# SpringReverbRev2_1_combined.net
KiCad netlist of a schematic drawn in EAGLE
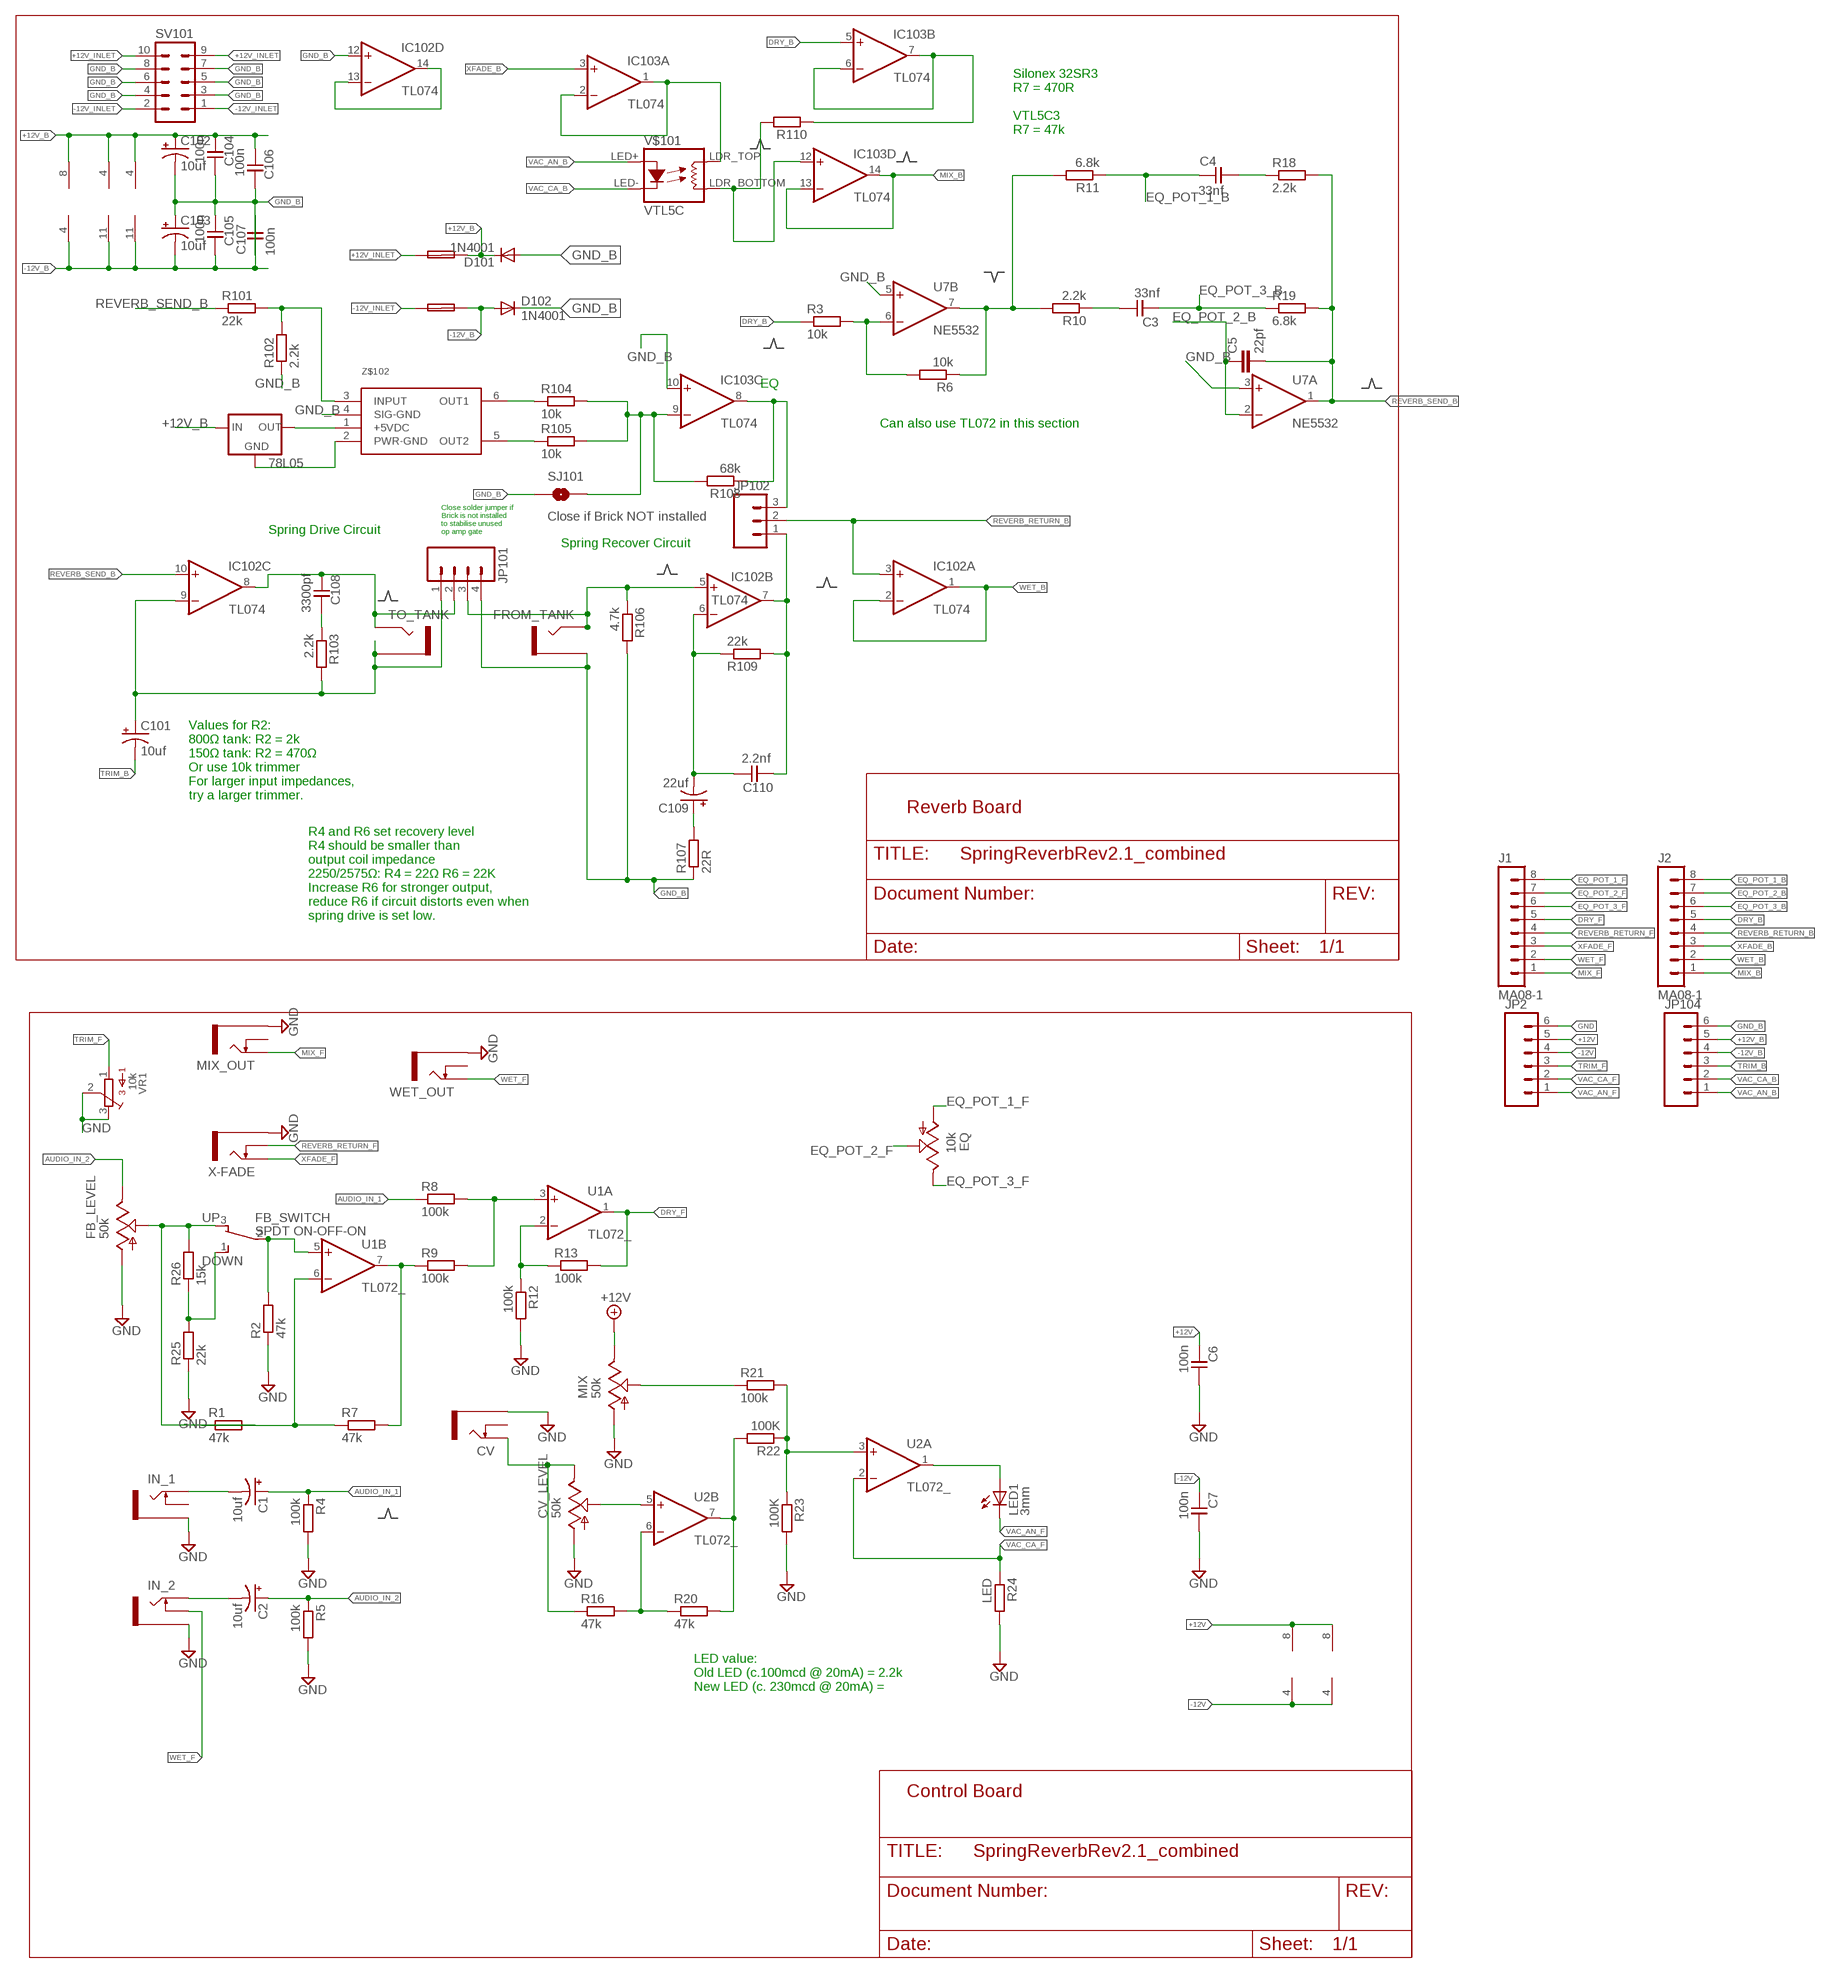
[diagram p0: schematic, sheet 1]

(export (version "E")
  (design (tool "Eeschema 10.0.6"))
  (components
    (comp (ref "78L05")
      (value "78LXX")
      (footprint "eagle-import:78LXX")
      (libsource (lib "eagle-import") (part "78LXX"))
    )
    (comp (ref "C1")
      (value "10uf")
      (footprint "eagle-import:050_020")
      (libsource (lib "eagle-import") (part "050"))
    )
    (comp (ref "C2")
      (value "10uf")
      (footprint "eagle-import:050_020")
      (libsource (lib "eagle-import") (part "050"))
    )
    (comp (ref "C3")
      (value "33nf")
      (footprint "eagle-import:C050-024X044")
      (libsource (lib "eagle-import") (part "C-EU050-024X044"))
    )
    (comp (ref "C4")
      (value "33nf")
      (footprint "eagle-import:C050-024X044")
      (libsource (lib "eagle-import") (part "C-EU050-024X044"))
    )
    (comp (ref "C5")
      (value "22pf")
      (footprint "eagle-import:050X030_025")
      (libsource (lib "eagle-import") (part "050X030_0251"))
    )
    (comp (ref "C6")
      (value "100n")
      (footprint "eagle-import:C050-024X044")
      (libsource (lib "eagle-import") (part "C-EU050-024X044"))
    )
    (comp (ref "C7")
      (value "100n")
      (footprint "eagle-import:C050-024X044")
      (libsource (lib "eagle-import") (part "C-EU050-024X044"))
    )
    (comp (ref "C101")
      (value "10uf")
      (footprint "eagle-import:CPOL-RADIAL-10UF-25V")
      (libsource (lib "eagle-import") (part "CAP_POLPTH2"))
    )
    (comp (ref "C102")
      (value "10uf")
      (footprint "eagle-import:CPOL-RADIAL-10UF-25V")
      (libsource (lib "eagle-import") (part "CAP_POLPTH2"))
    )
    (comp (ref "C103")
      (value "10uf")
      (footprint "eagle-import:CPOL-RADIAL-10UF-25V")
      (libsource (lib "eagle-import") (part "CAP_POLPTH2"))
    )
    (comp (ref "C104")
      (value "100n")
      (footprint "eagle-import:C050-024X044")
      (libsource (lib "eagle-import") (part "C-EU050-024X044"))
    )
    (comp (ref "C105")
      (value "100n")
      (footprint "eagle-import:C050-024X044")
      (libsource (lib "eagle-import") (part "C-EU050-024X044"))
    )
    (comp (ref "C106")
      (value "100n")
      (footprint "eagle-import:C050-024X044")
      (libsource (lib "eagle-import") (part "C-EU050-024X044"))
    )
    (comp (ref "C107")
      (value "100n")
      (footprint "eagle-import:C050-024X044")
      (libsource (lib "eagle-import") (part "C-EU050-024X044"))
    )
    (comp (ref "C108")
      (value "3300pf")
      (footprint "eagle-import:C050-024X044")
      (libsource (lib "eagle-import") (part "C-EU050-024X044"))
    )
    (comp (ref "C109")
      (value "22uf")
      (footprint "eagle-import:CPOL-RADIAL-10UF-25V")
      (libsource (lib "eagle-import") (part "CAP_POLPTH2"))
    )
    (comp (ref "C110")
      (value "2.2nf")
      (footprint "eagle-import:C050-024X044")
      (libsource (lib "eagle-import") (part "C-EU050-024X044"))
    )
    (comp (ref "CV")
      (value "THONKICONNNEW")
      (footprint "eagle-import:WQP-PJ301M-12_JACK")
      (libsource (lib "eagle-import") (part "THONKICONNNEW"))
    )
    (comp (ref "CV_LEVEL")
      (value "50k")
      (footprint "eagle-import:EVUF")
      (libsource (lib "eagle-import") (part "ALPHA-9MMAF2"))
    )
    (comp (ref "D101")
      (value "1N4001")
      (footprint "eagle-import:DO41-10")
      (libsource (lib "eagle-import") (part "1N4004"))
    )
    (comp (ref "D102")
      (value "1N4001")
      (footprint "eagle-import:DO41-10")
      (libsource (lib "eagle-import") (part "1N4004"))
    )
    (comp (ref "EQ")
      (value "10k")
      (footprint "eagle-import:EVUF")
      (libsource (lib "eagle-import") (part "ALPHA-9MMAF2"))
    )
    (comp (ref "F101")
      (value "FUSE")
      (footprint "eagle-import:C050H075X075")
      (libsource (lib "eagle-import") (part "PTC_FUSEPOLY_FUSE"))
    )
    (comp (ref "F102")
      (value "FUSE")
      (footprint "eagle-import:C050H075X075")
      (libsource (lib "eagle-import") (part "PTC_FUSEPOLY_FUSE"))
    )
    (comp (ref "FB_LEVEL")
      (value "50k")
      (footprint "eagle-import:EVUF")
      (libsource (lib "eagle-import") (part "ALPHA-9MMAF2"))
    )
    (comp (ref "FB_SWITCH")
      (value "SPDT ON-OFF-ON")
      (footprint "eagle-import:SPDT-VERTICAL-TOP-SUBMINI-MULTICOMP")
      (libsource (lib "eagle-import") (part "SPDT-VERTICAL-UPTOP-SUBMINI"))
    )
    (comp (ref "FROM_TANK")
      (value "CUI-RCJ_RCA_PHONO")
      (footprint "eagle-import:CUI-RCJ_RCA_PHONO")
      (libsource (lib "eagle-import") (part "CUI-RCJ_RCA_PHONO"))
    )
    (comp (ref "IC102")
      (value "TL074")
      (footprint "eagle-import:DIL14")
      (libsource (lib "eagle-import") (part "TL074P"))
    )
    (comp (ref "IC103")
      (value "TL074")
      (footprint "eagle-import:DIL14")
      (libsource (lib "eagle-import") (part "TL074P"))
    )
    (comp (ref "IN_1")
      (value "THONKICONNNEW")
      (footprint "eagle-import:WQP-PJ301M-12_JACK")
      (libsource (lib "eagle-import") (part "THONKICONNNEW"))
    )
    (comp (ref "IN_2")
      (value "THONKICONNNEW")
      (footprint "eagle-import:WQP-PJ301M-12_JACK")
      (libsource (lib "eagle-import") (part "THONKICONNNEW"))
    )
    (comp (ref "J1")
      (value "MA08-1")
      (footprint "eagle-import:MA08-1")
      (libsource (lib "eagle-import") (part "MA08-1"))
    )
    (comp (ref "J2")
      (value "MA08-1")
      (footprint "eagle-import:MA08-1")
      (libsource (lib "eagle-import") (part "MA08-1"))
    )
    (comp (ref "JP2")
      (value "M06SIP")
      (footprint "eagle-import:1X06")
      (libsource (lib "eagle-import") (part "M06SIP"))
    )
    (comp (ref "JP101")
      (value "M04POLAR")
      (footprint "eagle-import:MOLEX-1X4")
      (libsource (lib "eagle-import") (part "M04POLAR"))
    )
    (comp (ref "JP102")
      (value "M03LOCK_NO_SILK")
      (footprint "eagle-import:1X03_LOCK_NO_SILK")
      (libsource (lib "eagle-import") (part "M03LOCK_NO_SILK"))
    )
    (comp (ref "JP104")
      (value "M06SIP")
      (footprint "eagle-import:1X06")
      (libsource (lib "eagle-import") (part "M06SIP"))
    )
    (comp (ref "LED1")
      (value "3mm")
      (footprint "eagle-import:LED3MM")
      (libsource (lib "eagle-import") (part "LED3MM"))
    )
    (comp (ref "MIX")
      (value "50k")
      (footprint "eagle-import:EVUF")
      (libsource (lib "eagle-import") (part "ALPHA-9MMAF2"))
    )
    (comp (ref "MIX_OUT")
      (value "THONKICONNNEW")
      (footprint "eagle-import:WQP-PJ301M-12_JACK")
      (libsource (lib "eagle-import") (part "THONKICONNNEW"))
    )
    (comp (ref "R1")
      (value "47k")
      (footprint "eagle-import:7MM_RESISTOR")
      (libsource (lib "eagle-import") (part "RESISTOR7MM"))
    )
    (comp (ref "R2")
      (value "47k")
      (footprint "eagle-import:7MM_RESISTOR")
      (libsource (lib "eagle-import") (part "RESISTOR7MM"))
    )
    (comp (ref "R3")
      (value "10k")
      (footprint "eagle-import:7MM_RESISTOR")
      (libsource (lib "eagle-import") (part "RESISTOR7MM"))
    )
    (comp (ref "R4")
      (value "100k")
      (footprint "eagle-import:7MM_RESISTOR")
      (libsource (lib "eagle-import") (part "RESISTOR7MM"))
    )
    (comp (ref "R5")
      (value "100k")
      (footprint "eagle-import:7MM_RESISTOR")
      (libsource (lib "eagle-import") (part "RESISTOR7MM"))
    )
    (comp (ref "R6")
      (value "10k")
      (footprint "eagle-import:7MM_RESISTOR")
      (libsource (lib "eagle-import") (part "RESISTOR7MM"))
    )
    (comp (ref "R7")
      (value "47k")
      (footprint "eagle-import:7MM_RESISTOR")
      (libsource (lib "eagle-import") (part "RESISTOR7MM"))
    )
    (comp (ref "R8")
      (value "100k")
      (footprint "eagle-import:7MM_RESISTOR")
      (libsource (lib "eagle-import") (part "RESISTOR7MM"))
    )
    (comp (ref "R9")
      (value "100k")
      (footprint "eagle-import:7MM_RESISTOR")
      (libsource (lib "eagle-import") (part "RESISTOR7MM"))
    )
    (comp (ref "R10")
      (value "2.2k")
      (footprint "eagle-import:7MM_RESISTOR")
      (libsource (lib "eagle-import") (part "RESISTOR7MM"))
    )
    (comp (ref "R11")
      (value "6.8k")
      (footprint "eagle-import:7MM_RESISTOR")
      (libsource (lib "eagle-import") (part "RESISTOR7MM"))
    )
    (comp (ref "R12")
      (value "100k")
      (footprint "eagle-import:7MM_RESISTOR")
      (libsource (lib "eagle-import") (part "RESISTOR7MM"))
    )
    (comp (ref "R13")
      (value "100k")
      (footprint "eagle-import:7MM_RESISTOR")
      (libsource (lib "eagle-import") (part "RESISTOR7MM"))
    )
    (comp (ref "R16")
      (value "47k")
      (footprint "eagle-import:7MM_RESISTOR")
      (libsource (lib "eagle-import") (part "RESISTOR7MM"))
    )
    (comp (ref "R18")
      (value "2.2k")
      (footprint "eagle-import:7MM_RESISTOR")
      (libsource (lib "eagle-import") (part "RESISTOR7MM"))
    )
    (comp (ref "R19")
      (value "6.8k")
      (footprint "eagle-import:7MM_RESISTOR")
      (libsource (lib "eagle-import") (part "RESISTOR7MM"))
    )
    (comp (ref "R20")
      (value "47k")
      (footprint "eagle-import:7MM_RESISTOR")
      (libsource (lib "eagle-import") (part "RESISTOR7MM"))
    )
    (comp (ref "R21")
      (value "100k")
      (footprint "eagle-import:7MM_RESISTOR")
      (libsource (lib "eagle-import") (part "RESISTOR7MM"))
    )
    (comp (ref "R22")
      (value "100K")
      (footprint "eagle-import:7MM_RESISTOR")
      (libsource (lib "eagle-import") (part "RESISTOR7MM"))
    )
    (comp (ref "R23")
      (value "100K")
      (footprint "eagle-import:7MM_RESISTOR")
      (libsource (lib "eagle-import") (part "RESISTOR7MM"))
    )
    (comp (ref "R24")
      (value "LED")
      (footprint "eagle-import:7MM_RESISTOR")
      (libsource (lib "eagle-import") (part "RESISTOR7MM"))
    )
    (comp (ref "R25")
      (value "22k")
      (footprint "eagle-import:7MM_RESISTOR")
      (libsource (lib "eagle-import") (part "RESISTOR7MM"))
    )
    (comp (ref "R26")
      (value "15k")
      (footprint "eagle-import:7MM_RESISTOR")
      (libsource (lib "eagle-import") (part "RESISTOR7MM"))
    )
    (comp (ref "R101")
      (value "22k")
      (footprint "eagle-import:7MM_RESISTOR")
      (libsource (lib "eagle-import") (part "RESISTOR7MM"))
    )
    (comp (ref "R102")
      (value "2.2k")
      (footprint "eagle-import:7MM_RESISTOR")
      (libsource (lib "eagle-import") (part "RESISTOR7MM"))
    )
    (comp (ref "R103")
      (value "2.2k")
      (footprint "eagle-import:7MM_RESISTOR")
      (libsource (lib "eagle-import") (part "RESISTOR7MM"))
    )
    (comp (ref "R104")
      (value "10k")
      (footprint "eagle-import:7MM_RESISTOR")
      (libsource (lib "eagle-import") (part "RESISTOR7MM"))
    )
    (comp (ref "R105")
      (value "10k")
      (footprint "eagle-import:7MM_RESISTOR")
      (libsource (lib "eagle-import") (part "RESISTOR7MM"))
    )
    (comp (ref "R106")
      (value "4.7k")
      (footprint "eagle-import:7MM_RESISTOR")
      (libsource (lib "eagle-import") (part "RESISTOR7MM"))
    )
    (comp (ref "R107")
      (value "22R")
      (footprint "eagle-import:7MM_RESISTOR")
      (libsource (lib "eagle-import") (part "RESISTOR7MM"))
    )
    (comp (ref "R108")
      (value "68k")
      (footprint "eagle-import:7MM_RESISTOR")
      (libsource (lib "eagle-import") (part "RESISTOR7MM"))
    )
    (comp (ref "R109")
      (value "22k")
      (footprint "eagle-import:7MM_RESISTOR")
      (libsource (lib "eagle-import") (part "RESISTOR7MM"))
    )
    (comp (ref "R110")
      (value "RESISTOR7MM")
      (footprint "eagle-import:7MM_RESISTOR")
      (libsource (lib "eagle-import") (part "RESISTOR7MM"))
    )
    (comp (ref "SJ101")
      (value "Close if Brick NOT installed")
      (footprint "eagle-import:SJ_2S-NOTRACE")
      (libsource (lib "eagle-import") (part "SOLDERJUMPERNC2"))
    )
    (comp (ref "SV101")
      (value "10_PIN_HEADER")
      (footprint "eagle-import:MA05-2")
      (libsource (lib "eagle-import") (part "10_PIN_HEADER"))
    )
    (comp (ref "TO_TANK")
      (value "CUI-RCJ_RCA_PHONO")
      (footprint "eagle-import:CUI-RCJ_RCA_PHONO")
      (libsource (lib "eagle-import") (part "CUI-RCJ_RCA_PHONO"))
    )
    (comp (ref "U1")
      (value "TL072_")
      (footprint "eagle-import:DIL08")
      (libsource (lib "eagle-import") (part "TL072_"))
    )
    (comp (ref "U2")
      (value "TL072_")
      (footprint "eagle-import:DIL08")
      (libsource (lib "eagle-import") (part "TL072_"))
    )
    (comp (ref "U7")
      (value "NE5532")
      (footprint "eagle-import:DIL08")
      (libsource (lib "eagle-import") (part "TL072_"))
    )
    (comp (ref "V$101")
      (value "VTL5C")
      (footprint "eagle-import:VACTROL_COMPACT")
      (libsource (lib "eagle-import") (part "VACTROL_COMPACT"))
    )
    (comp (ref "VR1")
      (value "10k")
      (footprint "eagle-import:BOURNS_3362P_TRIMMER")
      (libsource (lib "eagle-import") (part "BOURNS_3362P_TRIMMERP"))
    )
    (comp (ref "WET_OUT")
      (value "THONKICONNNEW")
      (footprint "eagle-import:WQP-PJ301M-12_JACK")
      (libsource (lib "eagle-import") (part "THONKICONNNEW"))
    )
    (comp (ref "X-FADE")
      (value "THONKICONNNEW")
      (footprint "eagle-import:WQP-PJ301M-12_JACK")
      (libsource (lib "eagle-import") (part "THONKICONNNEW"))
    )
    (comp (ref "Z$102")
      (value "BTDR-2H")
      (footprint "eagle-import:BTDR-2H")
      (libsource (lib "eagle-import") (part "BTDR-2H"))
    )
  )
  (nets
    (net (code "1") (name "+12V") (class "Default")
      (node (ref "C6") (pin "2") (pinfunction "2_2") (pintype "passive"))
      (node (ref "JP2") (pin "5") (pinfunction "5_5") (pintype "passive"))
      (node (ref "MIX") (pin "3") (pinfunction "E_3") (pintype "passive"))
      (node (ref "U1") (pin "8") (pinfunction "V+_8") (pintype "power_in"))
      (node (ref "U2") (pin "8") (pinfunction "V+_8") (pintype "power_in"))
    )
    (net (code "2") (name "+12V_B") (class "Default")
      (node (ref "78L05") (pin "IN") (pinfunction "IN_IN") (pintype "input"))
      (node (ref "C102") (pin "1") (pinfunction "+_1") (pintype "passive"))
      (node (ref "C104") (pin "2") (pinfunction "2_2") (pintype "passive"))
      (node (ref "C106") (pin "2") (pinfunction "2_2") (pintype "passive"))
      (node (ref "D101") (pin "C") (pinfunction "C_C") (pintype "passive"))
      (node (ref "F101") (pin "1") (pinfunction "P$1_1") (pintype "bidirectional"))
      (node (ref "IC102") (pin "4") (pinfunction "V+_4") (pintype "power_in"))
      (node (ref "IC103") (pin "4") (pinfunction "V+_4") (pintype "power_in"))
      (node (ref "JP104") (pin "5") (pinfunction "5_5") (pintype "passive"))
      (node (ref "U7") (pin "8") (pinfunction "V+_8") (pintype "power_in"))
    )
    (net (code "3") (name "+12V_INLET") (class "Default")
      (node (ref "F101") (pin "2") (pinfunction "P$2_2") (pintype "bidirectional"))
      (node (ref "SV101") (pin "10") (pinfunction "10_10") (pintype "passive"))
      (node (ref "SV101") (pin "9") (pinfunction "9_9") (pintype "passive"))
    )
    (net (code "4") (name "-12V") (class "Default")
      (node (ref "C7") (pin "2") (pinfunction "2_2") (pintype "passive"))
      (node (ref "JP2") (pin "4") (pinfunction "4_4") (pintype "passive"))
      (node (ref "U1") (pin "4") (pinfunction "V-_4") (pintype "power_in"))
      (node (ref "U2") (pin "4") (pinfunction "V-_4") (pintype "power_in"))
    )
    (net (code "5") (name "-12V_B") (class "Default")
      (node (ref "C103") (pin "2") (pinfunction "-_2") (pintype "passive"))
      (node (ref "C105") (pin "1") (pinfunction "1_1") (pintype "passive"))
      (node (ref "C107") (pin "1") (pinfunction "1_1") (pintype "passive"))
      (node (ref "D102") (pin "A") (pinfunction "A_A") (pintype "passive"))
      (node (ref "F102") (pin "1") (pinfunction "P$1_1") (pintype "bidirectional"))
      (node (ref "IC102") (pin "11") (pinfunction "V-_11") (pintype "power_in"))
      (node (ref "IC103") (pin "11") (pinfunction "V-_11") (pintype "power_in"))
      (node (ref "JP104") (pin "4") (pinfunction "4_4") (pintype "passive"))
      (node (ref "U7") (pin "4") (pinfunction "V-_4") (pintype "power_in"))
    )
    (net (code "6") (name "-12V_INLET") (class "Default")
      (node (ref "F102") (pin "2") (pinfunction "P$2_2") (pintype "bidirectional"))
      (node (ref "SV101") (pin "1") (pinfunction "1_1") (pintype "passive"))
      (node (ref "SV101") (pin "2") (pinfunction "2_2") (pintype "passive"))
    )
    (net (code "7") (name "AUDIO_IN_1") (class "Default")
      (node (ref "C1") (pin "+") (pinfunction "+_+") (pintype "passive"))
      (node (ref "R4") (pin "1") (pinfunction "1_1") (pintype "passive"))
      (node (ref "R8") (pin "1") (pinfunction "1_1") (pintype "passive"))
    )
    (net (code "8") (name "AUDIO_IN_2") (class "Default")
      (node (ref "C2") (pin "+") (pinfunction "+_+") (pintype "passive"))
      (node (ref "FB_LEVEL") (pin "3") (pinfunction "E_3") (pintype "passive"))
      (node (ref "R5") (pin "1") (pinfunction "1_1") (pintype "passive"))
    )
    (net (code "9") (name "DRY_B") (class "Default")
      (node (ref "IC103") (pin "5") (pinfunction "+IN_5") (pintype "input"))
      (node (ref "J2") (pin "5") (pinfunction "5_5") (pintype "passive"))
      (node (ref "R3") (pin "1") (pinfunction "1_1") (pintype "passive"))
    )
    (net (code "10") (name "DRY_F") (class "Default")
      (node (ref "J1") (pin "5") (pinfunction "5_5") (pintype "passive"))
      (node (ref "R13") (pin "2") (pinfunction "2_2") (pintype "passive"))
      (node (ref "U1") (pin "1") (pinfunction "OUT_1") (pintype "output"))
    )
    (net (code "11") (name "EQ_POT_1_B") (class "Default")
      (node (ref "C4") (pin "2") (pinfunction "2_2") (pintype "passive"))
      (node (ref "J2") (pin "8") (pinfunction "8_8") (pintype "passive"))
      (node (ref "R11") (pin "1") (pinfunction "1_1") (pintype "passive"))
    )
    (net (code "12") (name "EQ_POT_1_F") (class "Default")
      (node (ref "EQ") (pin "1") (pinfunction "A_1") (pintype "passive"))
      (node (ref "J1") (pin "8") (pinfunction "8_8") (pintype "passive"))
    )
    (net (code "13") (name "EQ_POT_2_B") (class "Default")
      (node (ref "C5") (pin "1") (pinfunction "1_1") (pintype "passive"))
      (node (ref "J2") (pin "7") (pinfunction "7_7") (pintype "passive"))
      (node (ref "U7") (pin "2") (pinfunction "-IN_2") (pintype "input"))
    )
    (net (code "14") (name "EQ_POT_2_F") (class "Default")
      (node (ref "EQ") (pin "2") (pinfunction "S_2") (pintype "passive"))
      (node (ref "J1") (pin "7") (pinfunction "7_7") (pintype "passive"))
    )
    (net (code "15") (name "EQ_POT_3_B") (class "Default")
      (node (ref "C3") (pin "2") (pinfunction "2_2") (pintype "passive"))
      (node (ref "J2") (pin "6") (pinfunction "6_6") (pintype "passive"))
      (node (ref "R19") (pin "1") (pinfunction "1_1") (pintype "passive"))
    )
    (net (code "16") (name "EQ_POT_3_F") (class "Default")
      (node (ref "EQ") (pin "3") (pinfunction "E_3") (pintype "passive"))
      (node (ref "J1") (pin "6") (pinfunction "6_6") (pintype "passive"))
    )
    (net (code "17") (name "GND") (class "Default")
      (node (ref "C6") (pin "1") (pinfunction "1_1") (pintype "passive"))
      (node (ref "C7") (pin "1") (pinfunction "1_1") (pintype "passive"))
      (node (ref "CV") (pin "P$3_SLEEVE") (pinfunction "SLEEVE_P$3_SLEEVE") (pintype "passive"))
      (node (ref "CV_LEVEL") (pin "1") (pinfunction "A_1") (pintype "passive"))
      (node (ref "FB_LEVEL") (pin "1") (pinfunction "A_1") (pintype "passive"))
      (node (ref "IN_1") (pin "P$3_SLEEVE") (pinfunction "SLEEVE_P$3_SLEEVE") (pintype "passive"))
      (node (ref "IN_2") (pin "P$3_SLEEVE") (pinfunction "SLEEVE_P$3_SLEEVE") (pintype "passive"))
      (node (ref "JP2") (pin "6") (pinfunction "6_6") (pintype "passive"))
      (node (ref "MIX") (pin "1") (pinfunction "A_1") (pintype "passive"))
      (node (ref "MIX_OUT") (pin "P$3_SLEEVE") (pinfunction "SLEEVE_P$3_SLEEVE") (pintype "passive"))
      (node (ref "R12") (pin "2") (pinfunction "2_2") (pintype "passive"))
      (node (ref "R2") (pin "1") (pinfunction "1_1") (pintype "passive"))
      (node (ref "R23") (pin "2") (pinfunction "2_2") (pintype "passive"))
      (node (ref "R24") (pin "2") (pinfunction "2_2") (pintype "passive"))
      (node (ref "R25") (pin "1") (pinfunction "1_1") (pintype "passive"))
      (node (ref "R4") (pin "2") (pinfunction "2_2") (pintype "passive"))
      (node (ref "R5") (pin "2") (pinfunction "2_2") (pintype "passive"))
      (node (ref "VR1") (pin "2") (pinfunction "2_2") (pintype "passive"))
      (node (ref "VR1") (pin "3") (pinfunction "3_3") (pintype "passive"))
      (node (ref "WET_OUT") (pin "P$3_SLEEVE") (pinfunction "SLEEVE_P$3_SLEEVE") (pintype "passive"))
      (node (ref "X-FADE") (pin "P$3_SLEEVE") (pinfunction "SLEEVE_P$3_SLEEVE") (pintype "passive"))
    )
    (net (code "18") (name "GND_B") (class "Default")
      (node (ref "C102") (pin "2") (pinfunction "-_2") (pintype "passive"))
      (node (ref "C103") (pin "1") (pinfunction "+_1") (pintype "passive"))
      (node (ref "C104") (pin "1") (pinfunction "1_1") (pintype "passive"))
      (node (ref "C105") (pin "2") (pinfunction "2_2") (pintype "passive"))
      (node (ref "C106") (pin "1") (pinfunction "1_1") (pintype "passive"))
      (node (ref "C107") (pin "2") (pinfunction "2_2") (pintype "passive"))
      (node (ref "D101") (pin "A") (pinfunction "A_A") (pintype "passive"))
      (node (ref "D102") (pin "C") (pinfunction "C_C") (pintype "passive"))
      (node (ref "FROM_TANK") (pin "GND1") (pinfunction "SLEEVE_GND1") (pintype "passive"))
      (node (ref "FROM_TANK") (pin "GND2") (pinfunction "SLEEVE_GND2") (pintype "passive"))
      (node (ref "IC102") (pin "12") (pinfunction "+IN_12") (pintype "input"))
      (node (ref "IC103") (pin "10") (pinfunction "+IN_10") (pintype "input"))
      (node (ref "JP101") (pin "4") (pinfunction "4_4") (pintype "passive"))
      (node (ref "JP104") (pin "6") (pinfunction "6_6") (pintype "passive"))
      (node (ref "R102") (pin "1") (pinfunction "1_1") (pintype "passive"))
      (node (ref "R106") (pin "2") (pinfunction "2_2") (pintype "passive"))
      (node (ref "R107") (pin "1") (pinfunction "1_1") (pintype "passive"))
      (node (ref "SJ101") (pin "1") (pinfunction "1_1") (pintype "passive"))
      (node (ref "SV101") (pin "3") (pinfunction "3_3") (pintype "passive"))
      (node (ref "SV101") (pin "4") (pinfunction "4_4") (pintype "passive"))
      (node (ref "SV101") (pin "5") (pinfunction "5_5") (pintype "passive"))
      (node (ref "SV101") (pin "6") (pinfunction "6_6") (pintype "passive"))
      (node (ref "SV101") (pin "7") (pinfunction "7_7") (pintype "passive"))
      (node (ref "SV101") (pin "8") (pinfunction "8_8") (pintype "passive"))
      (node (ref "U7") (pin "3") (pinfunction "+IN_3") (pintype "input"))
      (node (ref "U7") (pin "5") (pinfunction "+IN_5") (pintype "input"))
      (node (ref "Z$102") (pin "4") (pinfunction "SIG-GND_4") (pintype "bidirectional"))
    )
    (net (code "19") (name "MIX_B") (class "Default")
      (node (ref "IC103") (pin "13") (pinfunction "-IN_13") (pintype "input"))
      (node (ref "IC103") (pin "14") (pinfunction "OUT_14") (pintype "output"))
      (node (ref "J2") (pin "1") (pinfunction "1_1") (pintype "passive"))
    )
    (net (code "20") (name "MIX_F") (class "Default")
      (node (ref "J1") (pin "1") (pinfunction "1_1") (pintype "passive"))
      (node (ref "MIX_OUT") (pin "P$1_TIP") (pinfunction "TIP_P$1_TIP") (pintype "passive"))
    )
    (net (code "21") (name "Net-(C3-Pad1)") (class "Default")
      (node (ref "C3") (pin "1") (pinfunction "1_1") (pintype "passive"))
      (node (ref "R10") (pin "1") (pinfunction "1_1") (pintype "passive"))
    )
    (net (code "22") (name "Net-(C4-Pad1)") (class "Default")
      (node (ref "C4") (pin "1") (pinfunction "1_1") (pintype "passive"))
      (node (ref "R18") (pin "1") (pinfunction "1_1") (pintype "passive"))
    )
    (net (code "23") (name "Net-(C101-+)") (class "Default")
      (node (ref "C101") (pin "1") (pinfunction "+_1") (pintype "passive"))
      (node (ref "IC102") (pin "9") (pinfunction "-IN_9") (pintype "input"))
      (node (ref "JP101") (pin "1") (pinfunction "1_1") (pintype "passive"))
      (node (ref "R103") (pin "2") (pinfunction "2_2") (pintype "passive"))
      (node (ref "TO_TANK") (pin "GND1") (pinfunction "SLEEVE_GND1") (pintype "passive"))
      (node (ref "TO_TANK") (pin "GND2") (pinfunction "SLEEVE_GND2") (pintype "passive"))
    )
    (net (code "24") (name "Net-(C108-Pad1)") (class "Default")
      (node (ref "C108") (pin "1") (pinfunction "1_1") (pintype "passive"))
      (node (ref "R103") (pin "1") (pinfunction "1_1") (pintype "passive"))
    )
    (net (code "25") (name "Net-(C109-+)") (class "Default")
      (node (ref "C109") (pin "1") (pinfunction "+_1") (pintype "passive"))
      (node (ref "R107") (pin "2") (pinfunction "2_2") (pintype "passive"))
    )
    (net (code "26") (name "Net-(C109--)") (class "Default")
      (node (ref "C109") (pin "2") (pinfunction "-_2") (pintype "passive"))
      (node (ref "C110") (pin "1") (pinfunction "1_1") (pintype "passive"))
      (node (ref "IC102") (pin "6") (pinfunction "-IN_6") (pintype "input"))
      (node (ref "R109") (pin "1") (pinfunction "1_1") (pintype "passive"))
    )
    (net (code "27") (name "Net-(CV-TIP)") (class "Default")
      (node (ref "CV") (pin "P$1_TIP") (pinfunction "TIP_P$1_TIP") (pintype "passive"))
      (node (ref "CV_LEVEL") (pin "3") (pinfunction "E_3") (pintype "passive"))
      (node (ref "R16") (pin "1") (pinfunction "1_1") (pintype "passive"))
    )
    (net (code "28") (name "Net-(CV_LEVEL-S)") (class "Default")
      (node (ref "CV_LEVEL") (pin "2") (pinfunction "S_2") (pintype "passive"))
      (node (ref "U2") (pin "5") (pinfunction "+IN_5") (pintype "input"))
    )
    (net (code "29") (name "Net-(FB_LEVEL-S)") (class "Default")
      (node (ref "FB_LEVEL") (pin "2") (pinfunction "S_2") (pintype "passive"))
      (node (ref "FB_SWITCH") (pin "3") (pinfunction "3_3") (pintype "passive"))
      (node (ref "R1") (pin "2") (pinfunction "2_2") (pintype "passive"))
      (node (ref "R26") (pin "2") (pinfunction "2_2") (pintype "passive"))
    )
    (net (code "30") (name "Net-(FB_SWITCH-Pad1)") (class "Default")
      (node (ref "FB_SWITCH") (pin "1") (pinfunction "1_1") (pintype "passive"))
      (node (ref "R25") (pin "2") (pinfunction "2_2") (pintype "passive"))
      (node (ref "R26") (pin "1") (pinfunction "1_1") (pintype "passive"))
    )
    (net (code "31") (name "Net-(FROM_TANK-TIP)") (class "Default")
      (node (ref "FROM_TANK") (pin "+V") (pinfunction "TIP_+V") (pintype "passive"))
      (node (ref "IC102") (pin "5") (pinfunction "+IN_5") (pintype "input"))
      (node (ref "JP101") (pin "3") (pinfunction "3_3") (pintype "passive"))
      (node (ref "R106") (pin "1") (pinfunction "1_1") (pintype "passive"))
    )
    (net (code "32") (name "Net-(IC102B-OUT)") (class "Default")
      (node (ref "C110") (pin "2") (pinfunction "2_2") (pintype "passive"))
      (node (ref "IC102") (pin "7") (pinfunction "OUT_7") (pintype "output"))
      (node (ref "JP102") (pin "1") (pinfunction "1_1") (pintype "passive"))
      (node (ref "R109") (pin "2") (pinfunction "2_2") (pintype "passive"))
    )
    (net (code "33") (name "Net-(IC102C-OUT)") (class "Default")
      (node (ref "C108") (pin "2") (pinfunction "2_2") (pintype "passive"))
      (node (ref "IC102") (pin "8") (pinfunction "OUT_8") (pintype "output"))
      (node (ref "JP101") (pin "2") (pinfunction "2_2") (pintype "passive"))
      (node (ref "TO_TANK") (pin "+V") (pinfunction "TIP_+V") (pintype "passive"))
    )
    (net (code "34") (name "Net-(IC102D--IN)") (class "Default")
      (node (ref "IC102") (pin "13") (pinfunction "-IN_13") (pintype "input"))
      (node (ref "IC102") (pin "14") (pinfunction "OUT_14") (pintype "output"))
    )
    (net (code "35") (name "Net-(IC103A--IN)") (class "Default")
      (node (ref "IC103") (pin "1") (pinfunction "OUT_1") (pintype "output"))
      (node (ref "IC103") (pin "2") (pinfunction "-IN_2") (pintype "input"))
      (node (ref "V$101") (pin "LDR_TOP") (pinfunction "RES1_LDR_TOP") (pintype "passive"))
    )
    (net (code "36") (name "Net-(IC103B--IN)") (class "Default")
      (node (ref "IC103") (pin "6") (pinfunction "-IN_6") (pintype "input"))
      (node (ref "IC103") (pin "7") (pinfunction "OUT_7") (pintype "output"))
      (node (ref "R110") (pin "1") (pinfunction "1_1") (pintype "passive"))
    )
    (net (code "37") (name "Net-(IC103C--IN)") (class "Default")
      (node (ref "IC103") (pin "9") (pinfunction "-IN_9") (pintype "input"))
      (node (ref "R104") (pin "2") (pinfunction "2_2") (pintype "passive"))
      (node (ref "R105") (pin "2") (pinfunction "2_2") (pintype "passive"))
      (node (ref "R108") (pin "2") (pinfunction "2_2") (pintype "passive"))
      (node (ref "SJ101") (pin "2") (pinfunction "2_2") (pintype "passive"))
    )
    (net (code "38") (name "Net-(IC103C-OUT)") (class "Default")
      (node (ref "IC103") (pin "8") (pinfunction "OUT_8") (pintype "output"))
      (node (ref "JP102") (pin "3") (pinfunction "3_3") (pintype "passive"))
      (node (ref "R108") (pin "1") (pinfunction "1_1") (pintype "passive"))
    )
    (net (code "39") (name "Net-(IC103D-+IN)") (class "Default")
      (node (ref "IC103") (pin "12") (pinfunction "+IN_12") (pintype "input"))
      (node (ref "R110") (pin "2") (pinfunction "2_2") (pintype "passive"))
      (node (ref "V$101") (pin "LDR_BOTTOM") (pinfunction "RES2_LDR_BOTTOM") (pintype "passive"))
    )
    (net (code "40") (name "Net-(IN_1-TIP)") (class "Default")
      (node (ref "C1") (pin "-") (pinfunction "-_-") (pintype "passive"))
      (node (ref "IN_1") (pin "P$1_TIP") (pinfunction "TIP_P$1_TIP") (pintype "passive"))
    )
    (net (code "41") (name "Net-(IN_2-TIP)") (class "Default")
      (node (ref "C2") (pin "-") (pinfunction "-_-") (pintype "passive"))
      (node (ref "IN_2") (pin "P$1_TIP") (pinfunction "TIP_P$1_TIP") (pintype "passive"))
    )
    (net (code "42") (name "Net-(MIX-S)") (class "Default")
      (node (ref "MIX") (pin "2") (pinfunction "S_2") (pintype "passive"))
      (node (ref "R21") (pin "1") (pinfunction "1_1") (pintype "passive"))
    )
    (net (code "43") (name "Net-(U1A-+IN)") (class "Default")
      (node (ref "R8") (pin "2") (pinfunction "2_2") (pintype "passive"))
      (node (ref "R9") (pin "2") (pinfunction "2_2") (pintype "passive"))
      (node (ref "U1") (pin "3") (pinfunction "+IN_3") (pintype "input"))
    )
    (net (code "44") (name "Net-(U1A--IN)") (class "Default")
      (node (ref "R12") (pin "1") (pinfunction "1_1") (pintype "passive"))
      (node (ref "R13") (pin "1") (pinfunction "1_1") (pintype "passive"))
      (node (ref "U1") (pin "2") (pinfunction "-IN_2") (pintype "input"))
    )
    (net (code "45") (name "Net-(U1B-+IN)") (class "Default")
      (node (ref "FB_SWITCH") (pin "2") (pinfunction "2_2") (pintype "passive"))
      (node (ref "R2") (pin "2") (pinfunction "2_2") (pintype "passive"))
      (node (ref "U1") (pin "5") (pinfunction "+IN_5") (pintype "input"))
    )
    (net (code "46") (name "Net-(U1B--IN)") (class "Default")
      (node (ref "R1") (pin "1") (pinfunction "1_1") (pintype "passive"))
      (node (ref "R7") (pin "1") (pinfunction "1_1") (pintype "passive"))
      (node (ref "U1") (pin "6") (pinfunction "-IN_6") (pintype "input"))
    )
    (net (code "47") (name "Net-(U1B-OUT)") (class "Default")
      (node (ref "R7") (pin "2") (pinfunction "2_2") (pintype "passive"))
      (node (ref "R9") (pin "1") (pinfunction "1_1") (pintype "passive"))
      (node (ref "U1") (pin "7") (pinfunction "OUT_7") (pintype "output"))
    )
    (net (code "48") (name "Net-(U2A-+IN)") (class "Default")
      (node (ref "R21") (pin "2") (pinfunction "2_2") (pintype "passive"))
      (node (ref "R22") (pin "1") (pinfunction "1_1") (pintype "passive"))
      (node (ref "R23") (pin "1") (pinfunction "1_1") (pintype "passive"))
      (node (ref "U2") (pin "3") (pinfunction "+IN_3") (pintype "input"))
    )
    (net (code "49") (name "Net-(U2A-OUT)") (class "Default")
      (node (ref "LED1") (pin "A") (pinfunction "A_A") (pintype "passive"))
      (node (ref "U2") (pin "1") (pinfunction "OUT_1") (pintype "output"))
    )
    (net (code "50") (name "Net-(U2B--IN)") (class "Default")
      (node (ref "R16") (pin "2") (pinfunction "2_2") (pintype "passive"))
      (node (ref "R20") (pin "1") (pinfunction "1_1") (pintype "passive"))
      (node (ref "U2") (pin "6") (pinfunction "-IN_6") (pintype "input"))
    )
    (net (code "51") (name "Net-(U2B-OUT)") (class "Default")
      (node (ref "R20") (pin "2") (pinfunction "2_2") (pintype "passive"))
      (node (ref "R22") (pin "2") (pinfunction "2_2") (pintype "passive"))
      (node (ref "U2") (pin "7") (pinfunction "OUT_7") (pintype "output"))
    )
    (net (code "52") (name "Net-(U7B--IN)") (class "Default")
      (node (ref "R3") (pin "2") (pinfunction "2_2") (pintype "passive"))
      (node (ref "R6") (pin "2") (pinfunction "2_2") (pintype "passive"))
      (node (ref "U7") (pin "6") (pinfunction "-IN_6") (pintype "input"))
    )
    (net (code "53") (name "Net-(U7B-OUT)") (class "Default")
      (node (ref "R10") (pin "2") (pinfunction "2_2") (pintype "passive"))
      (node (ref "R11") (pin "2") (pinfunction "2_2") (pintype "passive"))
      (node (ref "R6") (pin "1") (pinfunction "1_1") (pintype "passive"))
      (node (ref "U7") (pin "7") (pinfunction "OUT_7") (pintype "output"))
    )
    (net (code "54") (name "Net-(Z$102-+5VDC)") (class "Default")
      (node (ref "78L05") (pin "OUT") (pinfunction "OUT_OUT") (pintype "passive"))
      (node (ref "Z$102") (pin "1") (pinfunction "+5VDC_1") (pintype "bidirectional"))
    )
    (net (code "55") (name "Net-(Z$102-INPUT)") (class "Default")
      (node (ref "R101") (pin "2") (pinfunction "2_2") (pintype "passive"))
      (node (ref "R102") (pin "2") (pinfunction "2_2") (pintype "passive"))
      (node (ref "Z$102") (pin "3") (pinfunction "INPUT_3") (pintype "bidirectional"))
    )
    (net (code "56") (name "Net-(Z$102-OUT1)") (class "Default")
      (node (ref "R104") (pin "1") (pinfunction "1_1") (pintype "passive"))
      (node (ref "Z$102") (pin "6") (pinfunction "OUT1_6") (pintype "bidirectional"))
    )
    (net (code "57") (name "Net-(Z$102-OUT2)") (class "Default")
      (node (ref "R105") (pin "1") (pinfunction "1_1") (pintype "passive"))
      (node (ref "Z$102") (pin "5") (pinfunction "OUT2_5") (pintype "bidirectional"))
    )
    (net (code "58") (name "Net-(Z$102-PWR-GND)") (class "Default")
      (node (ref "78L05") (pin "GND") (pinfunction "GND_GND") (pintype "input"))
      (node (ref "Z$102") (pin "2") (pinfunction "PWR-GND_2") (pintype "bidirectional"))
    )
    (net (code "59") (name "REVERB_RETURN_B") (class "Default")
      (node (ref "IC102") (pin "3") (pinfunction "+IN_3") (pintype "input"))
      (node (ref "J2") (pin "4") (pinfunction "4_4") (pintype "passive"))
      (node (ref "JP102") (pin "2") (pinfunction "2_2") (pintype "passive"))
    )
    (net (code "60") (name "REVERB_RETURN_F") (class "Default")
      (node (ref "J1") (pin "4") (pinfunction "4_4") (pintype "passive"))
      (node (ref "X-FADE") (pin "P$2_SWITCH") (pinfunction "SWITCH_P$2_SWITCH") (pintype "passive"))
    )
    (net (code "61") (name "REVERB_SEND_B") (class "Default")
      (node (ref "C5") (pin "2") (pinfunction "2_2") (pintype "passive"))
      (node (ref "IC102") (pin "10") (pinfunction "+IN_10") (pintype "input"))
      (node (ref "R101") (pin "1") (pinfunction "1_1") (pintype "passive"))
      (node (ref "R18") (pin "2") (pinfunction "2_2") (pintype "passive"))
      (node (ref "R19") (pin "2") (pinfunction "2_2") (pintype "passive"))
      (node (ref "U7") (pin "1") (pinfunction "OUT_1") (pintype "output"))
    )
    (net (code "62") (name "TRIM_B") (class "Default")
      (node (ref "C101") (pin "2") (pinfunction "-_2") (pintype "passive"))
      (node (ref "JP104") (pin "3") (pinfunction "3_3") (pintype "passive"))
    )
    (net (code "63") (name "TRIM_F") (class "Default")
      (node (ref "JP2") (pin "3") (pinfunction "3_3") (pintype "passive"))
      (node (ref "VR1") (pin "1") (pinfunction "1_1") (pintype "passive"))
    )
    (net (code "64") (name "VAC_AN_B") (class "Default")
      (node (ref "JP104") (pin "1") (pinfunction "1_1") (pintype "passive"))
      (node (ref "V$101") (pin "LED+") (pinfunction "LED+_LED+") (pintype "passive"))
    )
    (net (code "65") (name "VAC_AN_F") (class "Default")
      (node (ref "JP2") (pin "1") (pinfunction "1_1") (pintype "passive"))
      (node (ref "LED1") (pin "K") (pinfunction "C_K") (pintype "passive"))
    )
    (net (code "66") (name "VAC_CA_B") (class "Default")
      (node (ref "JP104") (pin "2") (pinfunction "2_2") (pintype "passive"))
      (node (ref "V$101") (pin "LED-") (pinfunction "LED-_LED-") (pintype "passive"))
    )
    (net (code "67") (name "VAC_CA_F") (class "Default")
      (node (ref "JP2") (pin "2") (pinfunction "2_2") (pintype "passive"))
      (node (ref "R24") (pin "1") (pinfunction "1_1") (pintype "passive"))
      (node (ref "U2") (pin "2") (pinfunction "-IN_2") (pintype "input"))
    )
    (net (code "68") (name "WET_B") (class "Default")
      (node (ref "IC102") (pin "1") (pinfunction "OUT_1") (pintype "output"))
      (node (ref "IC102") (pin "2") (pinfunction "-IN_2") (pintype "input"))
      (node (ref "J2") (pin "2") (pinfunction "2_2") (pintype "passive"))
    )
    (net (code "69") (name "WET_F") (class "Default")
      (node (ref "IN_2") (pin "P$2_SWITCH") (pinfunction "SWITCH_P$2_SWITCH") (pintype "passive"))
      (node (ref "J1") (pin "2") (pinfunction "2_2") (pintype "passive"))
      (node (ref "WET_OUT") (pin "P$1_TIP") (pinfunction "TIP_P$1_TIP") (pintype "passive"))
    )
    (net (code "70") (name "XFADE_B") (class "Default")
      (node (ref "IC103") (pin "3") (pinfunction "+IN_3") (pintype "input"))
      (node (ref "J2") (pin "3") (pinfunction "3_3") (pintype "passive"))
    )
    (net (code "71") (name "XFADE_F") (class "Default")
      (node (ref "J1") (pin "3") (pinfunction "3_3") (pintype "passive"))
      (node (ref "X-FADE") (pin "P$1_TIP") (pinfunction "TIP_P$1_TIP") (pintype "passive"))
    )
    (net (code "72") (name "unconnected-(CV-SWITCH-PadP$2_SWITCH)") (class "Default")
      (node (ref "CV") (pin "P$2_SWITCH") (pinfunction "SWITCH_P$2_SWITCH") (pintype "passive"))
    )
    (net (code "73") (name "unconnected-(IN_1-SWITCH-PadP$2_SWITCH)") (class "Default")
      (node (ref "IN_1") (pin "P$2_SWITCH") (pinfunction "SWITCH_P$2_SWITCH") (pintype "passive"))
    )
    (net (code "74") (name "unconnected-(MIX_OUT-SWITCH-PadP$2_SWITCH)") (class "Default")
      (node (ref "MIX_OUT") (pin "P$2_SWITCH") (pinfunction "SWITCH_P$2_SWITCH") (pintype "passive"))
    )
    (net (code "75") (name "unconnected-(WET_OUT-SWITCH-PadP$2_SWITCH)") (class "Default")
      (node (ref "WET_OUT") (pin "P$2_SWITCH") (pinfunction "SWITCH_P$2_SWITCH") (pintype "passive"))
    )
  )
)
